# irsensor.net
KiCad netlist of a schematic drawn in EAGLE
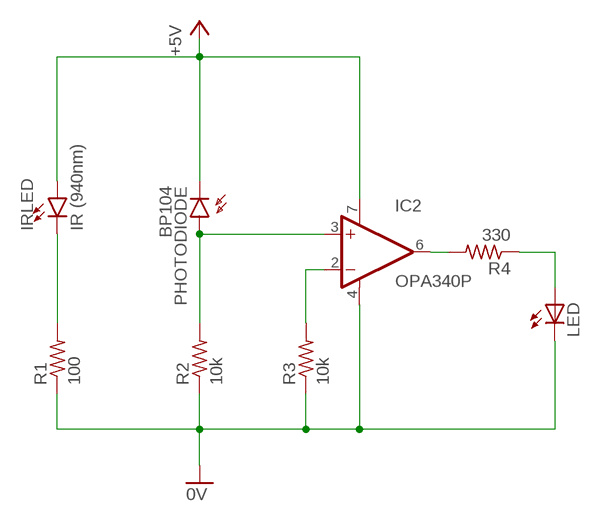
[diagram p0: schematic, sheet 1]

(export (version "E")
  (design (tool "Eeschema 10.0.6"))
  (components
    (comp (ref "IC2")
      (value "OPA340P")
      (footprint "eagle-import:DIL08")
      (fields (field (name "MPN") "OPA340PA"))
      (libsource (lib "eagle-import") (part "OPA340P"))
    )
    (comp (ref "IRLED")
      (value "IR (940nm)")
      (footprint "eagle-import:LED_5MM")
      (libsource (lib "eagle-import") (part "LED-IRTSAL6100"))
    )
    (comp (ref "LED")
      (value "LED5MM")
      (footprint "eagle-import:LED5MM")
      (libsource (lib "eagle-import") (part "LED5MM"))
    )
    (comp (ref "PHOTODIODE")
      (value "BP104")
      (footprint "eagle-import:BP104")
      (fields (field (name "MF") "VISHAY/TELEFUNKEN"))
      (libsource (lib "eagle-import") (part "BP104"))
    )
    (comp (ref "R1")
      (value "100")
      (footprint "eagle-import:0204V")
      (libsource (lib "eagle-import") (part "R-US_0204/2V"))
    )
    (comp (ref "R2")
      (value "10k")
      (footprint "eagle-import:0204V")
      (libsource (lib "eagle-import") (part "R-US_0204/2V"))
    )
    (comp (ref "R3")
      (value "10k")
      (footprint "eagle-import:0204V")
      (libsource (lib "eagle-import") (part "rcl_334_R-US_0204/2V"))
    )
    (comp (ref "R4")
      (value "330")
      (footprint "eagle-import:0204V")
      (libsource (lib "eagle-import") (part "rcl_334_R-US_0204/2V"))
    )
  )
  (nets
    (net (code "1") (name "+5V") (class "Default")
      (node (ref "IC2") (pin "7") (pinfunction "V+_7") (pintype "power_in"))
      (node (ref "IRLED") (pin "A") (pinfunction "A_A") (pintype "passive"))
      (node (ref "PHOTODIODE") (pin "K") (pinfunction "C_K") (pintype "passive"))
    )
    (net (code "2") (name "0V") (class "Default")
      (node (ref "IC2") (pin "4") (pinfunction "V-_4") (pintype "power_in"))
      (node (ref "LED") (pin "K") (pinfunction "C_K") (pintype "passive"))
      (node (ref "R1") (pin "1") (pinfunction "1_1") (pintype "passive"))
      (node (ref "R2") (pin "1") (pinfunction "1_1") (pintype "passive"))
      (node (ref "R3") (pin "1") (pinfunction "1_1") (pintype "passive"))
    )
    (net (code "3") (name "Net-(IC2-+IN)") (class "Default")
      (node (ref "IC2") (pin "3") (pinfunction "+IN_3") (pintype "input"))
      (node (ref "PHOTODIODE") (pin "A") (pinfunction "A_A") (pintype "passive"))
      (node (ref "R2") (pin "2") (pinfunction "2_2") (pintype "passive"))
    )
    (net (code "4") (name "Net-(IC2--IN)") (class "Default")
      (node (ref "IC2") (pin "2") (pinfunction "-IN_2") (pintype "input"))
      (node (ref "R3") (pin "2") (pinfunction "2_2") (pintype "passive"))
    )
    (net (code "5") (name "Net-(IC2-OUT)") (class "Default")
      (node (ref "IC2") (pin "6") (pinfunction "OUT_6") (pintype "output"))
      (node (ref "R4") (pin "2") (pinfunction "2_2") (pintype "passive"))
    )
    (net (code "6") (name "Net-(IRLED-C)") (class "Default")
      (node (ref "IRLED") (pin "K") (pinfunction "C_K") (pintype "passive"))
      (node (ref "R1") (pin "2") (pinfunction "2_2") (pintype "passive"))
    )
    (net (code "7") (name "Net-(LED-PadA)") (class "Default")
      (node (ref "LED") (pin "A") (pinfunction "A_A") (pintype "passive"))
      (node (ref "R4") (pin "1") (pinfunction "1_1") (pintype "passive"))
    )
  )
)
